# schematic.net
KiCad netlist of a schematic drawn in EAGLE
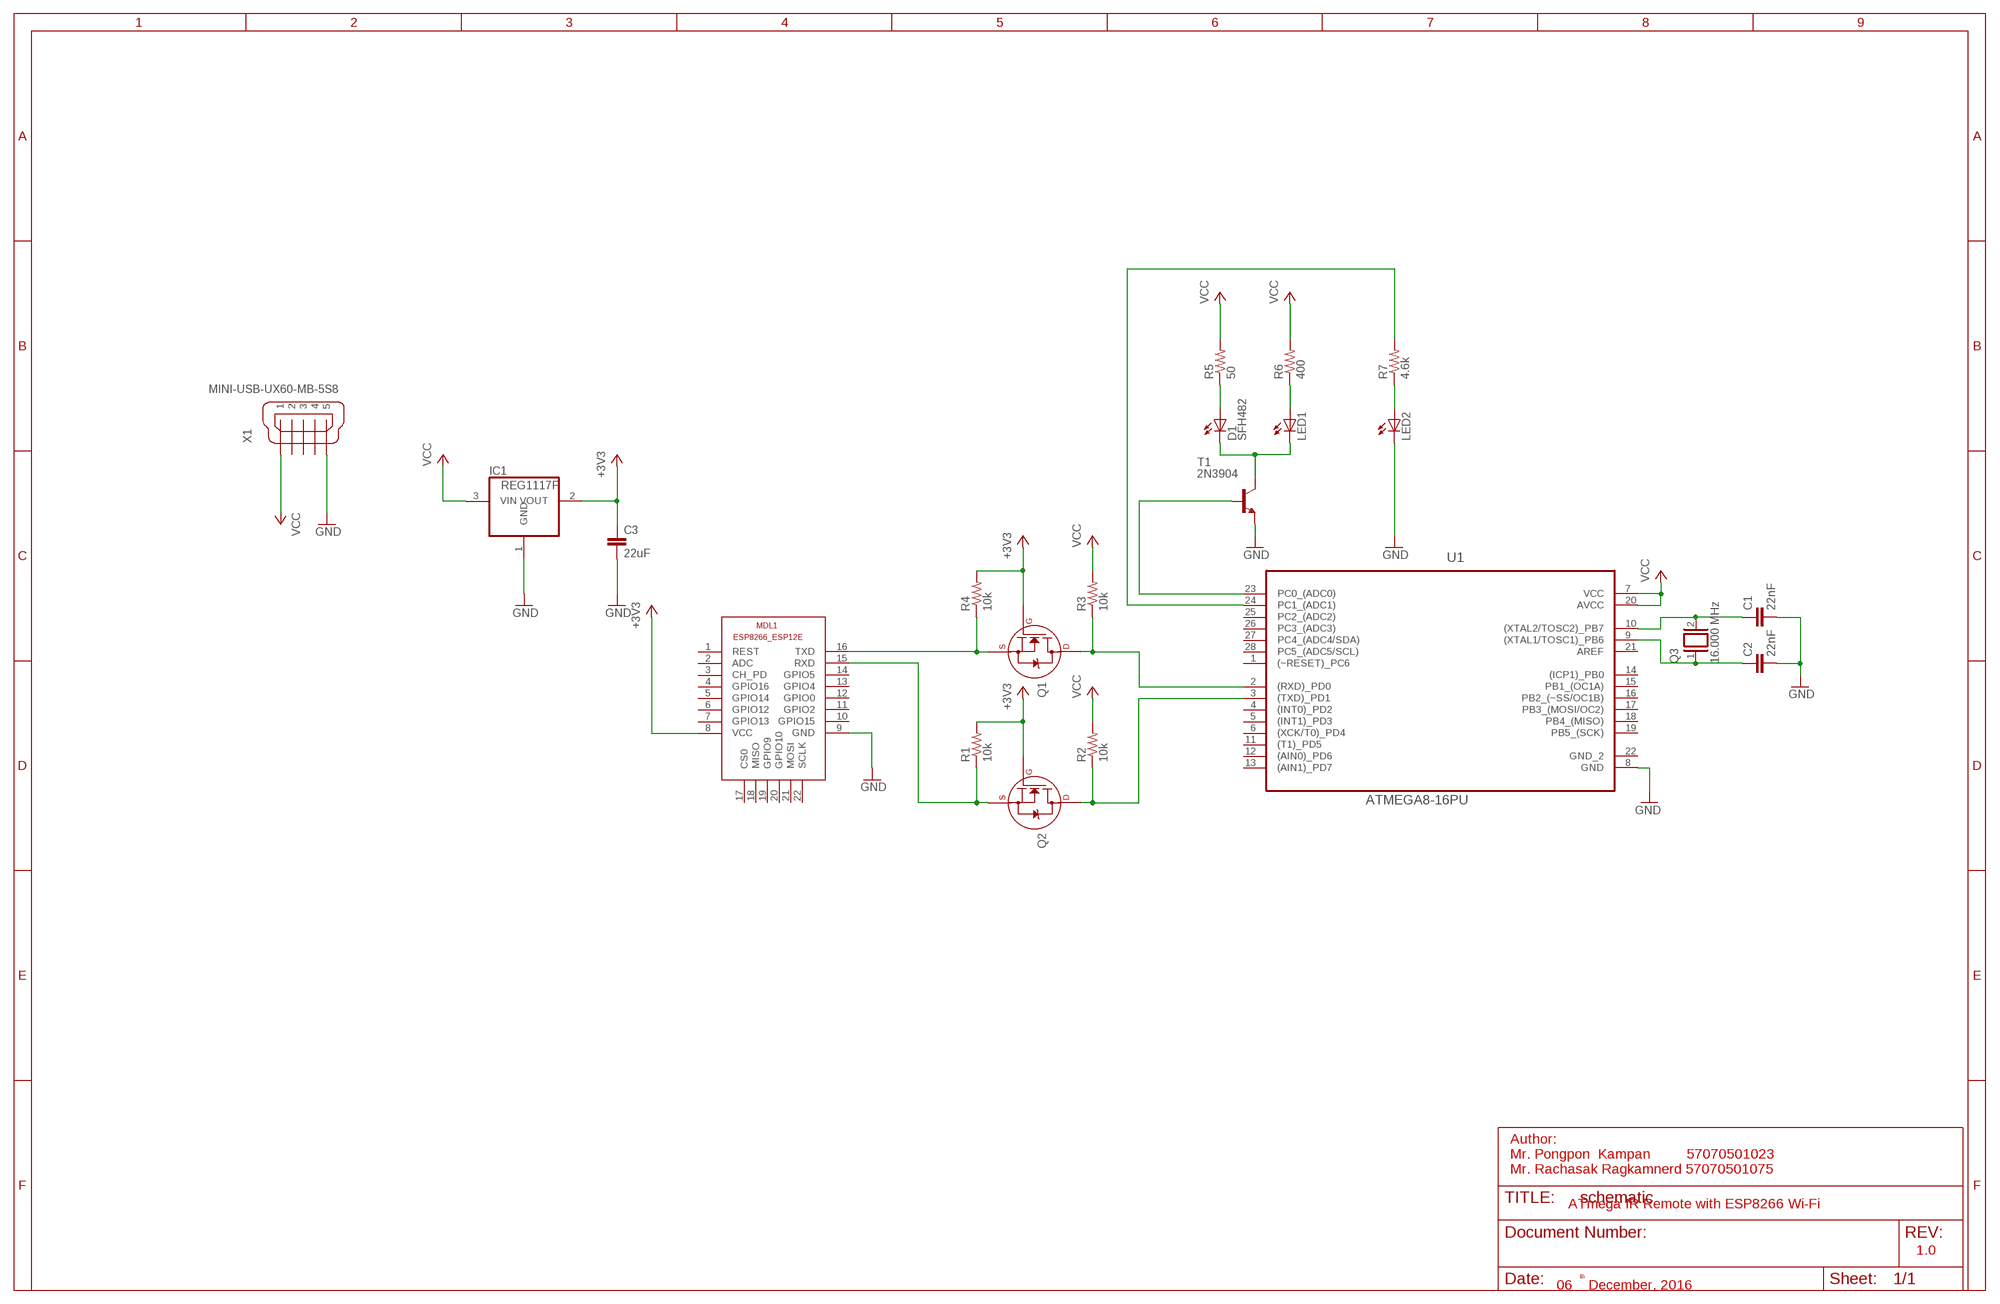
[diagram p0: schematic, sheet 1]

(export (version "E")
  (design (tool "Eeschema 10.0.6"))
  (components
    (comp (ref "C1")
      (value "22nF")
      (footprint "eagle-import:C2.5-3")
      (libsource (lib "eagle-import") (part "C2,5-3"))
    )
    (comp (ref "C2")
      (value "22nF")
      (footprint "eagle-import:C2.5-3")
      (libsource (lib "eagle-import") (part "C2,5-3"))
    )
    (comp (ref "C3")
      (value "22uF")
      (footprint "eagle-import:C0805")
      (libsource (lib "eagle-import") (part "C"))
    )
    (comp (ref "D1")
      (value "SFH482")
      (footprint "eagle-import:SFH482")
      (libsource (lib "eagle-import") (part "SFH482"))
    )
    (comp (ref "IC1")
      (value "REG1117F")
      (footprint "eagle-import:DD-3")
      (fields (field (name "MF") "TEXAS INSTRUMENTS") (field (name "MPN") "REG1117FAKTTT"))
      (libsource (lib "eagle-import") (part "REG1117F"))
    )
    (comp (ref "LED1")
      (value "LED5MM")
      (footprint "eagle-import:LED5MM")
      (libsource (lib "eagle-import") (part "LED5MM"))
    )
    (comp (ref "LED2")
      (value "LED5MM")
      (footprint "eagle-import:LED5MM")
      (libsource (lib "eagle-import") (part "LED5MM"))
    )
    (comp (ref "MDL1")
      (value "ESP8266-12EESP8266-ESP12E")
      (footprint "eagle-import:ESP8266-ESP12E")
      (libsource (lib "eagle-import") (part "ESP8266-12EESP8266-ESP12E"))
    )
    (comp (ref "Q1")
      (value "2N7000_TO92")
      (footprint "eagle-import:TO-92")
      (libsource (lib "eagle-import") (part "2N700_TO920"))
    )
    (comp (ref "Q2")
      (value "2N7000_TO92")
      (footprint "eagle-import:TO-92")
      (libsource (lib "eagle-import") (part "2N700_TO920"))
    )
    (comp (ref "Q3")
      (value "16.000 MHz")
      (footprint "eagle-import:Q")
      (libsource (lib "eagle-import") (part "XTAL"))
    )
    (comp (ref "R1")
      (value "10k")
      (footprint "eagle-import:AXIAL-0.3")
      (libsource (lib "eagle-import") (part "10KOHM-1/4W-1%(PTH)HORIZ"))
    )
    (comp (ref "R2")
      (value "10k")
      (footprint "eagle-import:AXIAL-0.3")
      (libsource (lib "eagle-import") (part "10KOHM-1/4W-1%(PTH)HORIZ"))
    )
    (comp (ref "R3")
      (value "10k")
      (footprint "eagle-import:AXIAL-0.3")
      (libsource (lib "eagle-import") (part "10KOHM-1/4W-1%(PTH)HORIZ"))
    )
    (comp (ref "R4")
      (value "10k")
      (footprint "eagle-import:AXIAL-0.3")
      (libsource (lib "eagle-import") (part "10KOHM-1/4W-1%(PTH)HORIZ"))
    )
    (comp (ref "R5")
      (value "50")
      (footprint "eagle-import:AXIAL-0.3")
      (libsource (lib "eagle-import") (part "1KOHM-1/4W-1%(PTH)"))
    )
    (comp (ref "R6")
      (value "400")
      (footprint "eagle-import:AXIAL-0.3")
      (libsource (lib "eagle-import") (part "1KOHM-1/4W-1%(PTH)"))
    )
    (comp (ref "R7")
      (value "4.6k")
      (footprint "eagle-import:AXIAL-0.3")
      (libsource (lib "eagle-import") (part "1KOHM-1/4W-1%(PTH)"))
    )
    (comp (ref "T1")
      (value "2N3904")
      (footprint "eagle-import:TO92")
      (libsource (lib "eagle-import") (part "2N3904"))
    )
    (comp (ref "U1")
      (value "ATMEGA8-16PU")
      (footprint "eagle-import:DIP254P762X457-28")
      (libsource (lib "eagle-import") (part "ATMEGA8-16PU"))
    )
    (comp (ref "X1")
      (value "MINI-USB-UX60-MB-5S8")
      (footprint "eagle-import:UX60-MB-5S8")
      (libsource (lib "eagle-import") (part "MINI-USB-UX60-MB-5S8"))
    )
  )
  (nets
    (net (code "1") (name "+3V3") (class "Default")
      (node (ref "C3") (pin "1") (pinfunction "1_1") (pintype "passive"))
      (node (ref "IC1") (pin "2") (pinfunction "VOUT_2") (pintype "output"))
      (node (ref "MDL1") (pin "8") (pinfunction "VCC_8") (pintype "bidirectional"))
      (node (ref "Q1") (pin "2") (pinfunction "G_2") (pintype "tri_state"))
      (node (ref "Q2") (pin "2") (pinfunction "G_2") (pintype "tri_state"))
      (node (ref "R1") (pin "P$2") (pinfunction "2_P$2") (pintype "passive"))
      (node (ref "R4") (pin "P$2") (pinfunction "2_P$2") (pintype "passive"))
    )
    (net (code "2") (name "GND") (class "Default")
      (node (ref "C1") (pin "2") (pinfunction "2_2") (pintype "passive"))
      (node (ref "C2") (pin "2") (pinfunction "2_2") (pintype "passive"))
      (node (ref "C3") (pin "2") (pinfunction "2_2") (pintype "passive"))
      (node (ref "IC1") (pin "1") (pinfunction "GND_1") (pintype "power_in"))
      (node (ref "LED2") (pin "K") (pinfunction "C_K") (pintype "passive"))
      (node (ref "MDL1") (pin "9") (pinfunction "GND_9") (pintype "bidirectional"))
      (node (ref "T1") (pin "3") (pinfunction "E_3") (pintype "passive"))
      (node (ref "U1") (pin "8") (pinfunction "GND_8") (pintype "passive"))
      (node (ref "X1") (pin "5") (pinfunction "5_5") (pintype "input"))
    )
    (net (code "3") (name "Net-(D1-C)") (class "Default")
      (node (ref "D1") (pin "K") (pinfunction "C_K") (pintype "passive"))
      (node (ref "LED1") (pin "K") (pinfunction "C_K") (pintype "passive"))
      (node (ref "T1") (pin "1") (pinfunction "C_1") (pintype "passive"))
    )
    (net (code "4") (name "Net-(MDL1-RXD)") (class "Default")
      (node (ref "MDL1") (pin "15") (pinfunction "RXD_15") (pintype "bidirectional"))
      (node (ref "Q2") (pin "1") (pinfunction "S_1") (pintype "bidirectional"))
      (node (ref "R1") (pin "P$1") (pinfunction "1_P$1") (pintype "passive"))
    )
    (net (code "5") (name "Net-(MDL1-TXD)") (class "Default")
      (node (ref "MDL1") (pin "16") (pinfunction "TXD_16") (pintype "bidirectional"))
      (node (ref "Q1") (pin "1") (pinfunction "S_1") (pintype "bidirectional"))
      (node (ref "R4") (pin "P$1") (pinfunction "1_P$1") (pintype "passive"))
    )
    (net (code "6") (name "Net-(Q1-D)") (class "Default")
      (node (ref "Q1") (pin "3") (pinfunction "D_3") (pintype "bidirectional"))
      (node (ref "R3") (pin "P$1") (pinfunction "1_P$1") (pintype "passive"))
      (node (ref "U1") (pin "2") (pinfunction "(RXD)_PD0_2") (pintype "bidirectional"))
    )
    (net (code "7") (name "Net-(Q2-D)") (class "Default")
      (node (ref "Q2") (pin "3") (pinfunction "D_3") (pintype "bidirectional"))
      (node (ref "R2") (pin "P$1") (pinfunction "1_P$1") (pintype "passive"))
      (node (ref "U1") (pin "3") (pinfunction "(TXD)_PD1_3") (pintype "bidirectional"))
    )
    (net (code "8") (name "Net-(R5-1)") (class "Default")
      (node (ref "D1") (pin "A") (pinfunction "A_A") (pintype "passive"))
      (node (ref "R5") (pin "P$1") (pinfunction "1_P$1") (pintype "passive"))
    )
    (net (code "9") (name "Net-(R6-1)") (class "Default")
      (node (ref "LED1") (pin "A") (pinfunction "A_A") (pintype "passive"))
      (node (ref "R6") (pin "P$1") (pinfunction "1_P$1") (pintype "passive"))
    )
    (net (code "10") (name "Net-(R7-1)") (class "Default")
      (node (ref "LED2") (pin "A") (pinfunction "A_A") (pintype "passive"))
      (node (ref "R7") (pin "P$1") (pinfunction "1_P$1") (pintype "passive"))
    )
    (net (code "11") (name "Net-(R7-2)") (class "Default")
      (node (ref "R7") (pin "P$2") (pinfunction "2_P$2") (pintype "passive"))
      (node (ref "U1") (pin "24") (pinfunction "PC1_(ADC1)_24") (pintype "bidirectional"))
    )
    (net (code "12") (name "Net-(T1-B)") (class "Default")
      (node (ref "T1") (pin "2") (pinfunction "B_2") (pintype "passive"))
      (node (ref "U1") (pin "23") (pinfunction "PC0_(ADC0)_23") (pintype "bidirectional"))
    )
    (net (code "13") (name "Net-(U1-(XTAL1{slash}TOSC1)_PB6)") (class "Default")
      (node (ref "C2") (pin "1") (pinfunction "1_1") (pintype "passive"))
      (node (ref "Q3") (pin "1") (pinfunction "1_1") (pintype "passive"))
      (node (ref "U1") (pin "9") (pinfunction "(XTAL1/TOSC1)_PB6_9") (pintype "input"))
    )
    (net (code "14") (name "Net-(U1-(XTAL2{slash}TOSC2)_PB7)") (class "Default")
      (node (ref "C1") (pin "1") (pinfunction "1_1") (pintype "passive"))
      (node (ref "Q3") (pin "2") (pinfunction "2_2") (pintype "passive"))
      (node (ref "U1") (pin "10") (pinfunction "(XTAL2/TOSC2)_PB7_10") (pintype "input"))
    )
    (net (code "15") (name "VCC") (class "Default")
      (node (ref "IC1") (pin "3") (pinfunction "VIN_3") (pintype "input"))
      (node (ref "R2") (pin "P$2") (pinfunction "2_P$2") (pintype "passive"))
      (node (ref "R3") (pin "P$2") (pinfunction "2_P$2") (pintype "passive"))
      (node (ref "R5") (pin "P$2") (pinfunction "2_P$2") (pintype "passive"))
      (node (ref "R6") (pin "P$2") (pinfunction "2_P$2") (pintype "passive"))
      (node (ref "U1") (pin "20") (pinfunction "AVCC_20") (pintype "power_in"))
      (node (ref "U1") (pin "7") (pinfunction "VCC_7") (pintype "power_in"))
      (node (ref "X1") (pin "1") (pinfunction "1_1") (pintype "input"))
    )
    (net (code "16") (name "unconnected-(MDL1-ADC-Pad2)") (class "Default")
      (node (ref "MDL1") (pin "2") (pinfunction "ADC_2") (pintype "bidirectional"))
    )
    (net (code "17") (name "unconnected-(MDL1-CH_PD-Pad3)") (class "Default")
      (node (ref "MDL1") (pin "3") (pinfunction "CH_PD_3") (pintype "bidirectional"))
    )
    (net (code "18") (name "unconnected-(MDL1-CS0-Pad17)") (class "Default")
      (node (ref "MDL1") (pin "17") (pinfunction "CS0_17") (pintype "bidirectional"))
    )
    (net (code "19") (name "unconnected-(MDL1-GPIO0-Pad12)") (class "Default")
      (node (ref "MDL1") (pin "12") (pinfunction "GPIO0_12") (pintype "bidirectional"))
    )
    (net (code "20") (name "unconnected-(MDL1-GPIO2-Pad11)") (class "Default")
      (node (ref "MDL1") (pin "11") (pinfunction "GPIO2_11") (pintype "bidirectional"))
    )
    (net (code "21") (name "unconnected-(MDL1-GPIO4-Pad13)") (class "Default")
      (node (ref "MDL1") (pin "13") (pinfunction "GPIO4_13") (pintype "bidirectional"))
    )
    (net (code "22") (name "unconnected-(MDL1-GPIO5-Pad14)") (class "Default")
      (node (ref "MDL1") (pin "14") (pinfunction "GPIO5_14") (pintype "bidirectional"))
    )
    (net (code "23") (name "unconnected-(MDL1-GPIO9-Pad19)") (class "Default")
      (node (ref "MDL1") (pin "19") (pinfunction "GPIO9_19") (pintype "bidirectional"))
    )
    (net (code "24") (name "unconnected-(MDL1-GPIO10-Pad20)") (class "Default")
      (node (ref "MDL1") (pin "20") (pinfunction "GPIO10_20") (pintype "bidirectional"))
    )
    (net (code "25") (name "unconnected-(MDL1-GPIO12-Pad6)") (class "Default")
      (node (ref "MDL1") (pin "6") (pinfunction "GPIO12_6") (pintype "bidirectional"))
    )
    (net (code "26") (name "unconnected-(MDL1-GPIO13-Pad7)") (class "Default")
      (node (ref "MDL1") (pin "7") (pinfunction "GPIO13_7") (pintype "bidirectional"))
    )
    (net (code "27") (name "unconnected-(MDL1-GPIO14-Pad5)") (class "Default")
      (node (ref "MDL1") (pin "5") (pinfunction "GPIO14_5") (pintype "bidirectional"))
    )
    (net (code "28") (name "unconnected-(MDL1-GPIO15-Pad10)") (class "Default")
      (node (ref "MDL1") (pin "10") (pinfunction "GPIO15_10") (pintype "bidirectional"))
    )
    (net (code "29") (name "unconnected-(MDL1-GPIO16-Pad4)") (class "Default")
      (node (ref "MDL1") (pin "4") (pinfunction "GPIO16_4") (pintype "bidirectional"))
    )
    (net (code "30") (name "unconnected-(MDL1-MISO-Pad18)") (class "Default")
      (node (ref "MDL1") (pin "18") (pinfunction "MISO_18") (pintype "bidirectional"))
    )
    (net (code "31") (name "unconnected-(MDL1-MOSI-Pad21)") (class "Default")
      (node (ref "MDL1") (pin "21") (pinfunction "MOSI_21") (pintype "bidirectional"))
    )
    (net (code "32") (name "unconnected-(MDL1-REST-Pad1)") (class "Default")
      (node (ref "MDL1") (pin "1") (pinfunction "REST_1") (pintype "bidirectional"))
    )
    (net (code "33") (name "unconnected-(MDL1-SCLK-Pad22)") (class "Default")
      (node (ref "MDL1") (pin "22") (pinfunction "SCLK_22") (pintype "bidirectional"))
    )
    (net (code "34") (name "unconnected-(U1-(AIN0)_PD6-Pad12)") (class "Default")
      (node (ref "U1") (pin "12") (pinfunction "(AIN0)_PD6_12") (pintype "bidirectional"))
    )
    (net (code "35") (name "unconnected-(U1-(AIN1)_PD7-Pad13)") (class "Default")
      (node (ref "U1") (pin "13") (pinfunction "(AIN1)_PD7_13") (pintype "bidirectional"))
    )
    (net (code "36") (name "unconnected-(U1-(ICP1)_PB0-Pad14)") (class "Default")
      (node (ref "U1") (pin "14") (pinfunction "(ICP1)_PB0_14") (pintype "bidirectional"))
    )
    (net (code "37") (name "unconnected-(U1-(INT0)_PD2-Pad4)") (class "Default")
      (node (ref "U1") (pin "4") (pinfunction "(INT0)_PD2_4") (pintype "bidirectional"))
    )
    (net (code "38") (name "unconnected-(U1-(INT1)_PD3-Pad5)") (class "Default")
      (node (ref "U1") (pin "5") (pinfunction "(INT1)_PD3_5") (pintype "bidirectional"))
    )
    (net (code "39") (name "unconnected-(U1-(T1)_PD5-Pad11)") (class "Default")
      (node (ref "U1") (pin "11") (pinfunction "(T1)_PD5_11") (pintype "bidirectional"))
    )
    (net (code "40") (name "unconnected-(U1-(XCK{slash}T0)_PD4-Pad6)") (class "Default")
      (node (ref "U1") (pin "6") (pinfunction "(XCK/T0)_PD4_6") (pintype "bidirectional"))
    )
    (net (code "41") (name "unconnected-(U1-(~{RESET})_PC6-Pad1)") (class "Default")
      (node (ref "U1") (pin "1") (pinfunction "(~{RESET})_PC6_1") (pintype "bidirectional"))
    )
    (net (code "42") (name "unconnected-(U1-AREF-Pad21)") (class "Default")
      (node (ref "U1") (pin "21") (pinfunction "AREF_21") (pintype "input"))
    )
    (net (code "43") (name "unconnected-(U1-GND_2-Pad22)") (class "Default")
      (node (ref "U1") (pin "22") (pinfunction "GND_2_22") (pintype "passive"))
    )
    (net (code "44") (name "unconnected-(U1-PB1_(OC1A)-Pad15)") (class "Default")
      (node (ref "U1") (pin "15") (pinfunction "PB1_(OC1A)_15") (pintype "bidirectional"))
    )
    (net (code "45") (name "unconnected-(U1-PB2_(~{SS{slash}OC1B})-Pad16)") (class "Default")
      (node (ref "U1") (pin "16") (pinfunction "PB2_(~{SS/OC1B})_16") (pintype "bidirectional"))
    )
    (net (code "46") (name "unconnected-(U1-PB3_(MOSI{slash}OC2)-Pad17)") (class "Default")
      (node (ref "U1") (pin "17") (pinfunction "PB3_(MOSI/OC2)_17") (pintype "bidirectional"))
    )
    (net (code "47") (name "unconnected-(U1-PB4_(MISO)-Pad18)") (class "Default")
      (node (ref "U1") (pin "18") (pinfunction "PB4_(MISO)_18") (pintype "bidirectional"))
    )
    (net (code "48") (name "unconnected-(U1-PB5_(SCK)-Pad19)") (class "Default")
      (node (ref "U1") (pin "19") (pinfunction "PB5_(SCK)_19") (pintype "bidirectional"))
    )
    (net (code "49") (name "unconnected-(U1-PC2_(ADC2)-Pad25)") (class "Default")
      (node (ref "U1") (pin "25") (pinfunction "PC2_(ADC2)_25") (pintype "bidirectional"))
    )
    (net (code "50") (name "unconnected-(U1-PC3_(ADC3)-Pad26)") (class "Default")
      (node (ref "U1") (pin "26") (pinfunction "PC3_(ADC3)_26") (pintype "bidirectional"))
    )
    (net (code "51") (name "unconnected-(U1-PC4_(ADC4{slash}SDA)-Pad27)") (class "Default")
      (node (ref "U1") (pin "27") (pinfunction "PC4_(ADC4/SDA)_27") (pintype "bidirectional"))
    )
    (net (code "52") (name "unconnected-(U1-PC5_(ADC5{slash}SCL)-Pad28)") (class "Default")
      (node (ref "U1") (pin "28") (pinfunction "PC5_(ADC5/SCL)_28") (pintype "bidirectional"))
    )
    (net (code "53") (name "unconnected-(X1-Pad2)") (class "Default")
      (node (ref "X1") (pin "2") (pinfunction "2_2") (pintype "input"))
    )
    (net (code "54") (name "unconnected-(X1-Pad3)") (class "Default")
      (node (ref "X1") (pin "3") (pinfunction "3_3") (pintype "input"))
    )
    (net (code "55") (name "unconnected-(X1-Pad4)") (class "Default")
      (node (ref "X1") (pin "4") (pinfunction "4_4") (pintype "input"))
    )
  )
)
